# Pressure_Transducers.net
KiCad netlist of a schematic drawn in Altium Designer
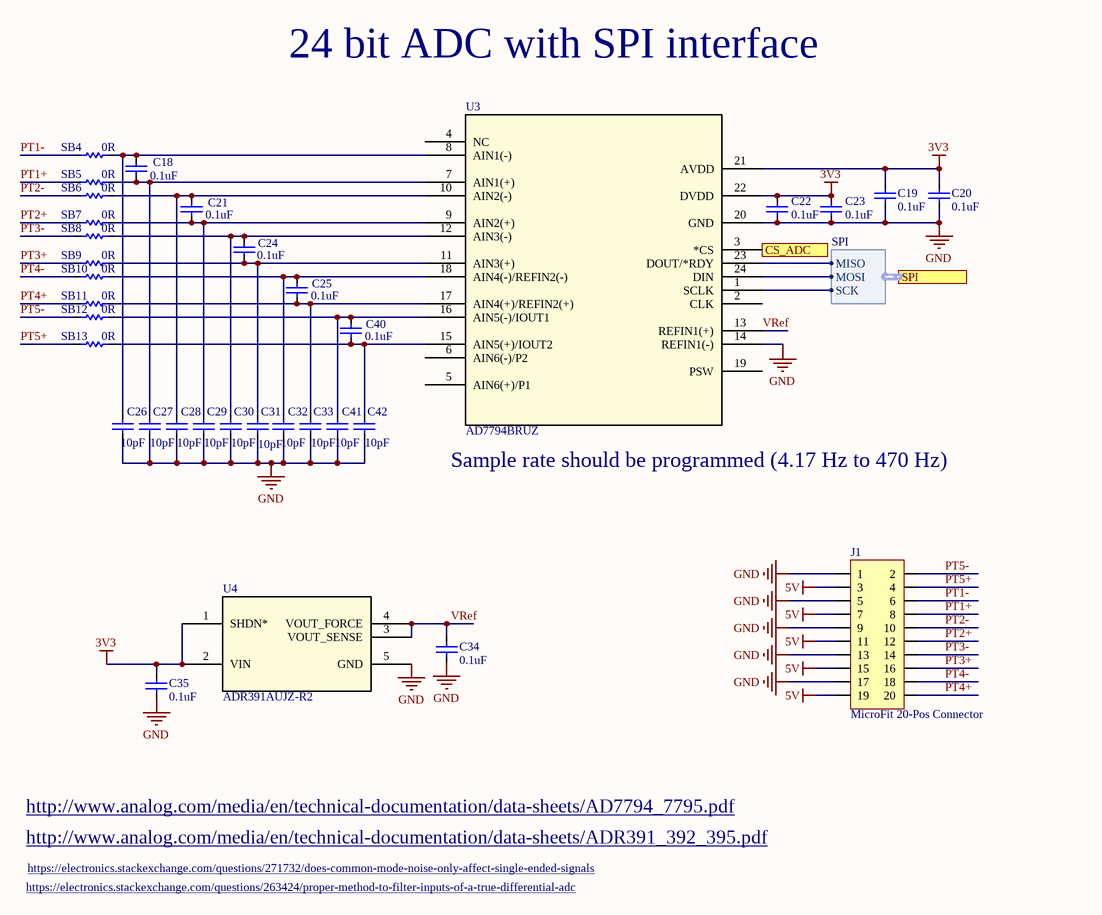
[diagram p0: Pressure_Transducers.SchDoc]

(export (version "E")
  (design (tool "Eeschema 10.0.6"))
  (components
    (comp (ref "C18")
      (value "0.1uF")
      (footprint "CAP_0603")
      (fields (field (name "Comment") "Cap"))
      (libsource (lib "RPL_POWER") (part "Cap"))
    )
    (comp (ref "C19")
      (value "0.1uF")
      (footprint "CAP_0603")
      (fields (field (name "Comment") "Cap"))
      (libsource (lib "RPL_POWER") (part "Cap"))
    )
    (comp (ref "C20")
      (value "0.1uF")
      (footprint "CAP_0603")
      (fields (field (name "Comment") "Cap"))
      (libsource (lib "RPL_POWER") (part "Cap"))
    )
    (comp (ref "C21")
      (value "0.1uF")
      (footprint "CAP_0603")
      (fields (field (name "Comment") "Cap"))
      (libsource (lib "RPL_POWER") (part "Cap"))
    )
    (comp (ref "C22")
      (value "0.1uF")
      (footprint "CAP_0603")
      (fields (field (name "Comment") "Cap"))
      (libsource (lib "RPL_POWER") (part "Cap"))
    )
    (comp (ref "C23")
      (value "0.1uF")
      (footprint "CAP_0603")
      (fields (field (name "Comment") "Cap"))
      (libsource (lib "RPL_POWER") (part "Cap"))
    )
    (comp (ref "C24")
      (value "0.1uF")
      (footprint "CAP_0603")
      (fields (field (name "Comment") "Cap"))
      (libsource (lib "RPL_POWER") (part "Cap"))
    )
    (comp (ref "C25")
      (value "0.1uF")
      (footprint "CAP_0603")
      (fields (field (name "Comment") "Cap"))
      (libsource (lib "RPL_POWER") (part "Cap"))
    )
    (comp (ref "C26")
      (value "10pF")
      (footprint "CAP_0603")
      (fields (field (name "Comment") "Cap"))
      (libsource (lib "RPL_POWER") (part "Cap"))
    )
    (comp (ref "C27")
      (value "10pF")
      (footprint "CAP_0603")
      (fields (field (name "Comment") "Cap"))
      (libsource (lib "RPL_POWER") (part "Cap"))
    )
    (comp (ref "C28")
      (value "10pF")
      (footprint "CAP_0603")
      (fields (field (name "Comment") "Cap"))
      (libsource (lib "RPL_POWER") (part "Cap"))
    )
    (comp (ref "C29")
      (value "10pF")
      (footprint "CAP_0603")
      (fields (field (name "Comment") "Cap"))
      (libsource (lib "RPL_POWER") (part "Cap"))
    )
    (comp (ref "C30")
      (value "10pF")
      (footprint "CAP_0603")
      (fields (field (name "Comment") "Cap"))
      (libsource (lib "RPL_POWER") (part "Cap"))
    )
    (comp (ref "C31")
      (value "10pF")
      (footprint "CAP_0603")
      (fields (field (name "Comment") "Cap"))
      (libsource (lib "RPL_POWER") (part "Cap"))
    )
    (comp (ref "C32")
      (value "10pF")
      (footprint "CAP_0603")
      (fields (field (name "Comment") "Cap"))
      (libsource (lib "RPL_POWER") (part "Cap"))
    )
    (comp (ref "C33")
      (value "10pF")
      (footprint "CAP_0603")
      (fields (field (name "Comment") "Cap"))
      (libsource (lib "RPL_POWER") (part "Cap"))
    )
    (comp (ref "C34")
      (value "0.1uF")
      (footprint "CAP_0603")
      (fields (field (name "Comment") "Cap"))
      (libsource (lib "RPL_POWER") (part "Cap"))
    )
    (comp (ref "C35")
      (value "0.1uF")
      (footprint "CAP_0603")
      (fields (field (name "Comment") "Cap"))
      (libsource (lib "RPL_POWER") (part "Cap"))
    )
    (comp (ref "C40")
      (value "0.1uF")
      (footprint "CAP_0603")
      (fields (field (name "Comment") "Cap"))
      (libsource (lib "RPL_POWER") (part "Cap"))
    )
    (comp (ref "C41")
      (value "10pF")
      (footprint "CAP_0603")
      (fields (field (name "Comment") "Cap"))
      (libsource (lib "RPL_POWER") (part "Cap"))
    )
    (comp (ref "C42")
      (value "10pF")
      (footprint "CAP_0603")
      (fields (field (name "Comment") "Cap"))
      (libsource (lib "RPL_POWER") (part "Cap"))
    )
    (comp (ref "J1")
      (value "MicroFit 20-Pos Connector")
      (footprint "Microfit-20Pos")
      (description "Molex MicroFit 20-Pos Connector")
      (libsource (lib "LaunchyRIOComponents") (part "Micro-Fit 20Pos"))
    )
    (comp (ref "SB4")
      (value "0R")
      (footprint "SB-2pos")
      (fields (field (name "Comment") "Res"))
      (libsource (lib "RPL_POWER") (part "Res"))
    )
    (comp (ref "SB5")
      (value "0R")
      (footprint "SB-2pos")
      (fields (field (name "Comment") "Res"))
      (libsource (lib "RPL_POWER") (part "Res"))
    )
    (comp (ref "SB6")
      (value "0R")
      (footprint "SB-2pos")
      (fields (field (name "Comment") "Res"))
      (libsource (lib "RPL_POWER") (part "Res"))
    )
    (comp (ref "SB7")
      (value "0R")
      (footprint "SB-2pos")
      (fields (field (name "Comment") "Res"))
      (libsource (lib "RPL_POWER") (part "Res"))
    )
    (comp (ref "SB8")
      (value "0R")
      (footprint "SB-2pos")
      (fields (field (name "Comment") "Res"))
      (libsource (lib "RPL_POWER") (part "Res"))
    )
    (comp (ref "SB9")
      (value "0R")
      (footprint "SB-2pos")
      (fields (field (name "Comment") "Res"))
      (libsource (lib "RPL_POWER") (part "Res"))
    )
    (comp (ref "SB10")
      (value "0R")
      (footprint "SB-2pos")
      (fields (field (name "Comment") "Res"))
      (libsource (lib "RPL_POWER") (part "Res"))
    )
    (comp (ref "SB11")
      (value "0R")
      (footprint "SB-2pos")
      (fields (field (name "Comment") "Res"))
      (libsource (lib "RPL_POWER") (part "Res"))
    )
    (comp (ref "SB12")
      (value "0R")
      (footprint "SB-2pos")
      (fields (field (name "Comment") "Res"))
      (libsource (lib "RPL_POWER") (part "Res"))
    )
    (comp (ref "SB13")
      (value "0R")
      (footprint "SB-2pos")
      (fields (field (name "Comment") "Res"))
      (libsource (lib "RPL_POWER") (part "Res"))
    )
    (comp (ref "U3")
      (value "AD7794BRUZ")
      (footprint "RU_24")
      (description "Imported")
      (libsource (lib "LaunchyRIOComponents") (part "AD7794BRUZ"))
    )
    (comp (ref "U4")
      (value "ADR391AUJZ-R2")
      (footprint "UJ_5")
      (description "Imported")
      (libsource (lib "LaunchyRIOComponents") (part "ADR391AUJZ-R2"))
    )
  )
  (nets
    (net (code "2") (name "/CS_ADC") (class "Default")
      (node (ref "U3") (pin "3") (pinfunction "*CS_3") (pintype "passive"))
    )
    (net (code "3") (name "/MISO") (class "Default")
      (node (ref "U3") (pin "23") (pinfunction "DOUT/*RDY_23") (pintype "passive"))
    )
    (net (code "4") (name "/MOSI") (class "Default")
      (node (ref "U3") (pin "24") (pinfunction "DIN_24") (pintype "passive"))
    )
    (net (code "5") (name "/PT1+") (class "Default")
      (node (ref "J1") (pin "8") (pinfunction "8_8") (pintype "passive"))
      (node (ref "SB5") (pin "1") (pinfunction "1_1") (pintype "passive"))
    )
    (net (code "6") (name "/PT1-") (class "Default")
      (node (ref "J1") (pin "6") (pinfunction "6_6") (pintype "passive"))
      (node (ref "SB4") (pin "1") (pinfunction "1_1") (pintype "passive"))
    )
    (net (code "7") (name "/PT2+") (class "Default")
      (node (ref "J1") (pin "12") (pinfunction "12_12") (pintype "passive"))
      (node (ref "SB7") (pin "1") (pinfunction "1_1") (pintype "passive"))
    )
    (net (code "8") (name "/PT2-") (class "Default")
      (node (ref "J1") (pin "10") (pinfunction "10_10") (pintype "passive"))
      (node (ref "SB6") (pin "1") (pinfunction "1_1") (pintype "passive"))
    )
    (net (code "9") (name "/PT3+") (class "Default")
      (node (ref "J1") (pin "16") (pinfunction "16_16") (pintype "passive"))
      (node (ref "SB9") (pin "1") (pinfunction "1_1") (pintype "passive"))
    )
    (net (code "10") (name "/PT3-") (class "Default")
      (node (ref "J1") (pin "14") (pinfunction "14_14") (pintype "passive"))
      (node (ref "SB8") (pin "1") (pinfunction "1_1") (pintype "passive"))
    )
    (net (code "11") (name "/PT4+") (class "Default")
      (node (ref "J1") (pin "20") (pinfunction "20_20") (pintype "passive"))
      (node (ref "SB11") (pin "1") (pinfunction "1_1") (pintype "passive"))
    )
    (net (code "12") (name "/PT4-") (class "Default")
      (node (ref "J1") (pin "18") (pinfunction "18_18") (pintype "passive"))
      (node (ref "SB10") (pin "1") (pinfunction "1_1") (pintype "passive"))
    )
    (net (code "13") (name "/PT5+") (class "Default")
      (node (ref "J1") (pin "4") (pinfunction "4_4") (pintype "passive"))
      (node (ref "SB13") (pin "1") (pinfunction "1_1") (pintype "passive"))
    )
    (net (code "14") (name "/PT5-") (class "Default")
      (node (ref "J1") (pin "2") (pinfunction "2_2") (pintype "passive"))
      (node (ref "SB12") (pin "1") (pinfunction "1_1") (pintype "passive"))
    )
    (net (code "15") (name "/SCK") (class "Default")
      (node (ref "U3") (pin "1") (pinfunction "SCLK_1") (pintype "passive"))
    )
    (net (code "16") (name "/VRef") (class "Default")
      (node (ref "C34") (pin "2") (pinfunction "2_2") (pintype "passive"))
      (node (ref "U3") (pin "13") (pinfunction "REFIN1(+)_13") (pintype "passive"))
      (node (ref "U4") (pin "3") (pinfunction "VOUT_SENSE_3") (pintype "passive"))
      (node (ref "U4") (pin "4") (pinfunction "VOUT_FORCE_4") (pintype "passive"))
    )
    (net (code "18") (name "3V3") (class "Default")
      (node (ref "C19") (pin "2") (pinfunction "2_2") (pintype "passive"))
      (node (ref "C20") (pin "2") (pinfunction "2_2") (pintype "passive"))
      (node (ref "C22") (pin "2") (pinfunction "2_2") (pintype "passive"))
      (node (ref "C23") (pin "2") (pinfunction "2_2") (pintype "passive"))
      (node (ref "C35") (pin "2") (pinfunction "2_2") (pintype "passive"))
      (node (ref "U3") (pin "21") (pinfunction "AVDD_21") (pintype "passive"))
      (node (ref "U3") (pin "22") (pinfunction "DVDD_22") (pintype "passive"))
      (node (ref "U4") (pin "1") (pinfunction "SHDN*_1") (pintype "passive"))
      (node (ref "U4") (pin "2") (pinfunction "VIN_2") (pintype "passive"))
    )
    (net (code "19") (name "5V") (class "Default")
      (node (ref "J1") (pin "11") (pinfunction "11_11") (pintype "passive"))
      (node (ref "J1") (pin "15") (pinfunction "15_15") (pintype "passive"))
      (node (ref "J1") (pin "19") (pinfunction "19_19") (pintype "passive"))
      (node (ref "J1") (pin "3") (pinfunction "3_3") (pintype "passive"))
      (node (ref "J1") (pin "7") (pinfunction "7_7") (pintype "passive"))
    )
    (net (code "20") (name "GND") (class "Default")
      (node (ref "C19") (pin "1") (pinfunction "1_1") (pintype "passive"))
      (node (ref "C20") (pin "1") (pinfunction "1_1") (pintype "passive"))
      (node (ref "C22") (pin "1") (pinfunction "1_1") (pintype "passive"))
      (node (ref "C23") (pin "1") (pinfunction "1_1") (pintype "passive"))
      (node (ref "C26") (pin "1") (pinfunction "1_1") (pintype "passive"))
      (node (ref "C27") (pin "1") (pinfunction "1_1") (pintype "passive"))
      (node (ref "C28") (pin "1") (pinfunction "1_1") (pintype "passive"))
      (node (ref "C29") (pin "1") (pinfunction "1_1") (pintype "passive"))
      (node (ref "C30") (pin "1") (pinfunction "1_1") (pintype "passive"))
      (node (ref "C31") (pin "1") (pinfunction "1_1") (pintype "passive"))
      (node (ref "C32") (pin "1") (pinfunction "1_1") (pintype "passive"))
      (node (ref "C33") (pin "1") (pinfunction "1_1") (pintype "passive"))
      (node (ref "C34") (pin "1") (pinfunction "1_1") (pintype "passive"))
      (node (ref "C35") (pin "1") (pinfunction "1_1") (pintype "passive"))
      (node (ref "C41") (pin "1") (pinfunction "1_1") (pintype "passive"))
      (node (ref "C42") (pin "1") (pinfunction "1_1") (pintype "passive"))
      (node (ref "J1") (pin "1") (pinfunction "1_1") (pintype "passive"))
      (node (ref "J1") (pin "13") (pinfunction "13_13") (pintype "passive"))
      (node (ref "J1") (pin "17") (pinfunction "17_17") (pintype "passive"))
      (node (ref "J1") (pin "5") (pinfunction "5_5") (pintype "passive"))
      (node (ref "J1") (pin "9") (pinfunction "9_9") (pintype "passive"))
      (node (ref "U3") (pin "14") (pinfunction "REFIN1(-)_14") (pintype "passive"))
      (node (ref "U3") (pin "20") (pinfunction "GND_20") (pintype "passive"))
      (node (ref "U4") (pin "5") (pinfunction "GND_5") (pintype "passive"))
    )
    (net (code "21") (name "Net-(U3-AIN1(+))") (class "Default")
      (node (ref "C18") (pin "1") (pinfunction "1_1") (pintype "passive"))
      (node (ref "C27") (pin "2") (pinfunction "2_2") (pintype "passive"))
      (node (ref "SB5") (pin "2") (pinfunction "2_2") (pintype "passive"))
      (node (ref "U3") (pin "7") (pinfunction "AIN1(+)_7") (pintype "passive"))
    )
    (net (code "22") (name "Net-(U3-AIN1(-))") (class "Default")
      (node (ref "C18") (pin "2") (pinfunction "2_2") (pintype "passive"))
      (node (ref "C26") (pin "2") (pinfunction "2_2") (pintype "passive"))
      (node (ref "SB4") (pin "2") (pinfunction "2_2") (pintype "passive"))
      (node (ref "U3") (pin "8") (pinfunction "AIN1(-)_8") (pintype "passive"))
    )
    (net (code "23") (name "Net-(U3-AIN2(+))") (class "Default")
      (node (ref "C21") (pin "1") (pinfunction "1_1") (pintype "passive"))
      (node (ref "C29") (pin "2") (pinfunction "2_2") (pintype "passive"))
      (node (ref "SB7") (pin "2") (pinfunction "2_2") (pintype "passive"))
      (node (ref "U3") (pin "9") (pinfunction "AIN2(+)_9") (pintype "passive"))
    )
    (net (code "24") (name "Net-(U3-AIN2(-))") (class "Default")
      (node (ref "C21") (pin "2") (pinfunction "2_2") (pintype "passive"))
      (node (ref "C28") (pin "2") (pinfunction "2_2") (pintype "passive"))
      (node (ref "SB6") (pin "2") (pinfunction "2_2") (pintype "passive"))
      (node (ref "U3") (pin "10") (pinfunction "AIN2(-)_10") (pintype "passive"))
    )
    (net (code "25") (name "Net-(U3-AIN3(+))") (class "Default")
      (node (ref "C24") (pin "1") (pinfunction "1_1") (pintype "passive"))
      (node (ref "C31") (pin "2") (pinfunction "2_2") (pintype "passive"))
      (node (ref "SB9") (pin "2") (pinfunction "2_2") (pintype "passive"))
      (node (ref "U3") (pin "11") (pinfunction "AIN3(+)_11") (pintype "passive"))
    )
    (net (code "26") (name "Net-(U3-AIN3(-))") (class "Default")
      (node (ref "C24") (pin "2") (pinfunction "2_2") (pintype "passive"))
      (node (ref "C30") (pin "2") (pinfunction "2_2") (pintype "passive"))
      (node (ref "SB8") (pin "2") (pinfunction "2_2") (pintype "passive"))
      (node (ref "U3") (pin "12") (pinfunction "AIN3(-)_12") (pintype "passive"))
    )
    (net (code "27") (name "Net-(U3-AIN4(+){slash}REFIN2(+))") (class "Default")
      (node (ref "C25") (pin "1") (pinfunction "1_1") (pintype "passive"))
      (node (ref "C33") (pin "2") (pinfunction "2_2") (pintype "passive"))
      (node (ref "SB11") (pin "2") (pinfunction "2_2") (pintype "passive"))
      (node (ref "U3") (pin "17") (pinfunction "AIN4(+)/REFIN2(+)_17") (pintype "passive"))
    )
    (net (code "28") (name "Net-(U3-AIN4(-){slash}REFIN2(-))") (class "Default")
      (node (ref "C25") (pin "2") (pinfunction "2_2") (pintype "passive"))
      (node (ref "C32") (pin "2") (pinfunction "2_2") (pintype "passive"))
      (node (ref "SB10") (pin "2") (pinfunction "2_2") (pintype "passive"))
      (node (ref "U3") (pin "18") (pinfunction "AIN4(-)/REFIN2(-)_18") (pintype "passive"))
    )
    (net (code "29") (name "Net-(U3-AIN5(+){slash}IOUT2)") (class "Default")
      (node (ref "C40") (pin "1") (pinfunction "1_1") (pintype "passive"))
      (node (ref "C42") (pin "2") (pinfunction "2_2") (pintype "passive"))
      (node (ref "SB13") (pin "2") (pinfunction "2_2") (pintype "passive"))
      (node (ref "U3") (pin "15") (pinfunction "AIN5(+)/IOUT2_15") (pintype "passive"))
    )
    (net (code "30") (name "Net-(U3-AIN5(-){slash}IOUT1)") (class "Default")
      (node (ref "C40") (pin "2") (pinfunction "2_2") (pintype "passive"))
      (node (ref "C41") (pin "2") (pinfunction "2_2") (pintype "passive"))
      (node (ref "SB12") (pin "2") (pinfunction "2_2") (pintype "passive"))
      (node (ref "U3") (pin "16") (pinfunction "AIN5(-)/IOUT1_16") (pintype "passive"))
    )
    (net (code "31") (name "unconnected-(U3-AIN6(+){slash}P1-Pad5)") (class "Default")
      (node (ref "U3") (pin "5") (pinfunction "AIN6(+)/P1_5") (pintype "passive"))
    )
    (net (code "32") (name "unconnected-(U3-AIN6(-){slash}P2-Pad6)") (class "Default")
      (node (ref "U3") (pin "6") (pinfunction "AIN6(-)/P2_6") (pintype "passive"))
    )
    (net (code "33") (name "unconnected-(U3-CLK-Pad2)") (class "Default")
      (node (ref "U3") (pin "2") (pinfunction "CLK_2") (pintype "passive"))
    )
    (net (code "34") (name "unconnected-(U3-NC-Pad4)") (class "Default")
      (node (ref "U3") (pin "4") (pinfunction "NC_4") (pintype "passive"))
    )
    (net (code "35") (name "unconnected-(U3-PSW-Pad19)") (class "Default")
      (node (ref "U3") (pin "19") (pinfunction "PSW_19") (pintype "passive"))
    )
  )
)
